# TSC_PROIECT_SCHEMATIC.net
KiCad netlist of a schematic drawn in EAGLE
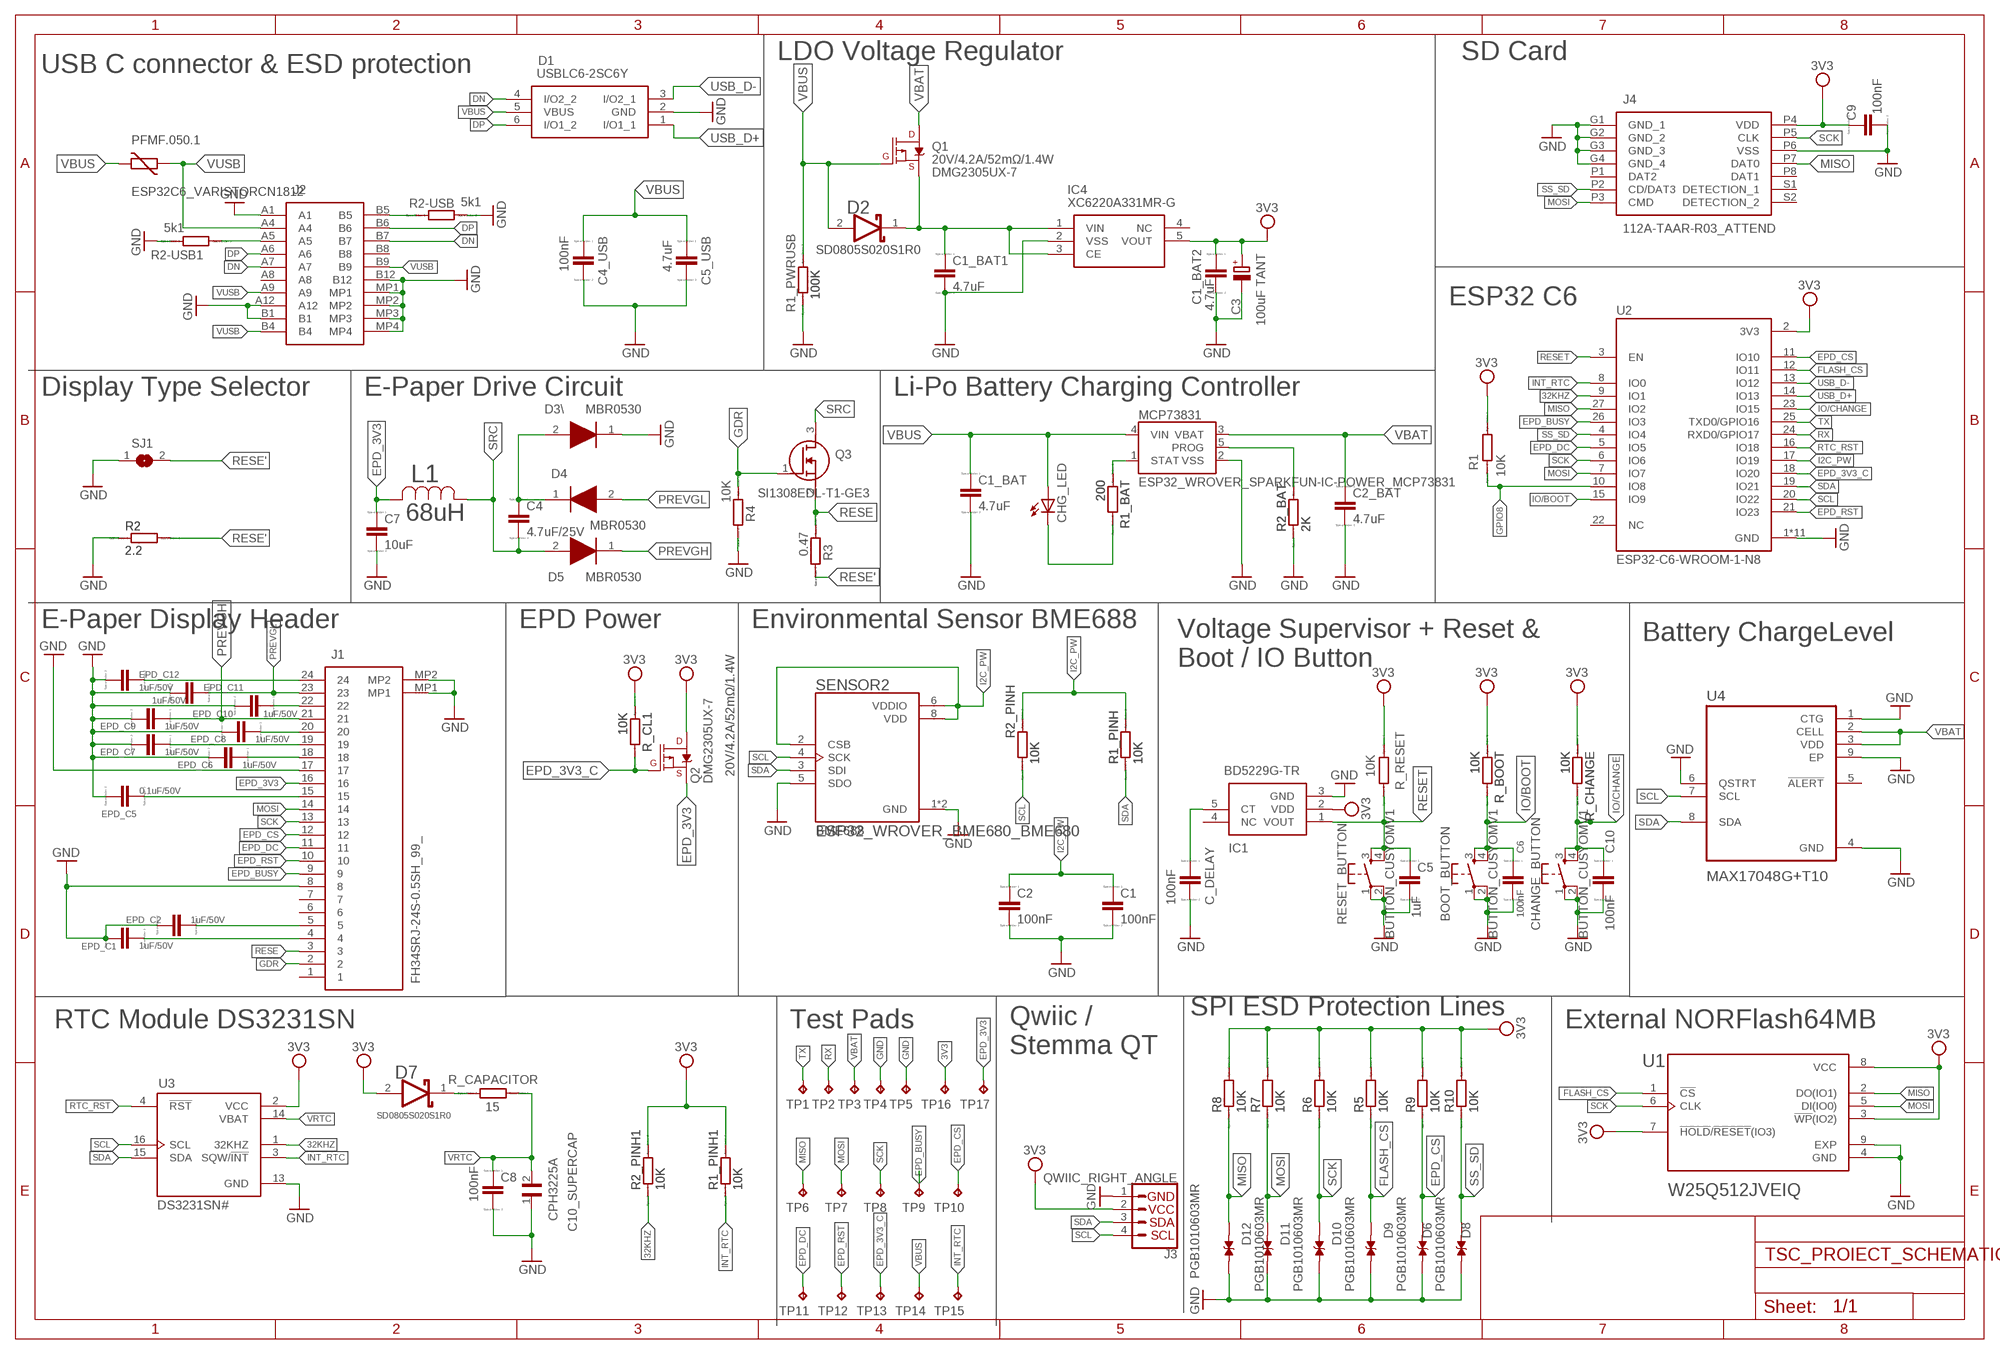
[diagram p0: schematic, sheet 1]

(export (version "E")
  (design (tool "Eeschema 10.0.6"))
  (components
    (comp (ref "BOOT_BUTTON")
      (value "BUTTON_CUSYOMV1")
      (footprint "eagle-import:MYBUTTON")
      (libsource (lib "eagle-import") (part "BUTTON_CUSYOMV1"))
    )
    (comp (ref "C1")
      (value "100nF")
      (footprint "eagle-import:ESP32_WROVER_EAGLE-LTSPICE_C0402")
      (libsource (lib "eagle-import") (part "ESP32_WROVER_EAGLE-LTSPICE_CC0402"))
    )
    (comp (ref "C1_BAT")
      (value "4.7uF")
      (footprint "eagle-import:ESP32_WROVER_EAGLE-LTSPICE_C0402")
      (libsource (lib "eagle-import") (part "EAGLE-LTSPICE_CC0402"))
    )
    (comp (ref "C1_BAT1")
      (value "4.7uF")
      (footprint "eagle-import:ESP32_WROVER_EAGLE-LTSPICE_C0402")
      (libsource (lib "eagle-import") (part "EAGLE-LTSPICE_CC0402"))
    )
    (comp (ref "C1_BAT2")
      (value "4.7uF")
      (footprint "eagle-import:ESP32_WROVER_EAGLE-LTSPICE_C0402")
      (libsource (lib "eagle-import") (part "ESP32_WROVER_EAGLE-LTSPICE_CC0402"))
    )
    (comp (ref "C2")
      (value "100nF")
      (footprint "eagle-import:ESP32_WROVER_EAGLE-LTSPICE_C0402")
      (libsource (lib "eagle-import") (part "ESP32_WROVER_EAGLE-LTSPICE_CC0402"))
    )
    (comp (ref "C2_BAT")
      (value "4.7uF")
      (footprint "eagle-import:ESP32_WROVER_EAGLE-LTSPICE_C0402")
      (libsource (lib "eagle-import") (part "EAGLE-LTSPICE_CC0402"))
    )
    (comp (ref "C3")
      (value "100uF TANT")
      (footprint "eagle-import:RCL_CT3528")
      (libsource (lib "eagle-import") (part "RCL_CPOL-EUCT3528"))
    )
    (comp (ref "C4")
      (value "4.7uF/25V")
      (footprint "eagle-import:ESP32_WROVER_EAGLE-LTSPICE_C0402")
      (libsource (lib "eagle-import") (part "ESP32_WROVER_EAGLE-LTSPICE_CC0402"))
    )
    (comp (ref "C4_USB")
      (value "100nF")
      (footprint "eagle-import:ESP32_WROVER_EAGLE-LTSPICE_C0402")
      (libsource (lib "eagle-import") (part "ESP32_WROVER_EAGLE-LTSPICE_CC0402"))
    )
    (comp (ref "C5")
      (value "1uF")
      (footprint "eagle-import:ESP32_WROVER_EAGLE-LTSPICE_C0402")
      (libsource (lib "eagle-import") (part "EAGLE-LTSPICE_CC0402"))
    )
    (comp (ref "C5_USB")
      (value "4.7uF")
      (footprint "eagle-import:ESP32_WROVER_EAGLE-LTSPICE_C0402")
      (libsource (lib "eagle-import") (part "ESP32_WROVER_EAGLE-LTSPICE_CC0402"))
    )
    (comp (ref "C6")
      (value "100nF")
      (footprint "eagle-import:ESP32_WROVER_EAGLE-LTSPICE_C0402")
      (libsource (lib "eagle-import") (part "EAGLE-LTSPICE_CC0402"))
    )
    (comp (ref "C7")
      (value "10uF")
      (footprint "eagle-import:ESP32_WROVER_EAGLE-LTSPICE_C0402")
      (libsource (lib "eagle-import") (part "ESP32_WROVER_EAGLE-LTSPICE_CC0402"))
    )
    (comp (ref "C8")
      (value "100nF")
      (footprint "eagle-import:ESP32_WROVER_EAGLE-LTSPICE_C0402")
      (libsource (lib "eagle-import") (part "ESP32_WROVER_EAGLE-LTSPICE_CC0402"))
    )
    (comp (ref "C9")
      (value "100nF")
      (footprint "eagle-import:ESP32_WROVER_EAGLE-LTSPICE_C0402")
      (libsource (lib "eagle-import") (part "EAGLE-LTSPICE_CC0402"))
    )
    (comp (ref "C10")
      (value "100nF")
      (footprint "eagle-import:ESP32_WROVER_EAGLE-LTSPICE_C0402")
      (libsource (lib "eagle-import") (part "EAGLE-LTSPICE_CC0402"))
    )
    (comp (ref "C10_SUPERCAP")
      (value "CPH3225A")
      (footprint "eagle-import:CAPCP3225X100N")
      (fields (field (name "MF") "Seiko Instruments"))
      (libsource (lib "eagle-import") (part "CPH3225A"))
    )
    (comp (ref "CHANGE_BUTTON")
      (value "BUTTON_CUSYOMV1")
      (footprint "eagle-import:MYBUTTON")
      (libsource (lib "eagle-import") (part "BUTTON_CUSYOMV1"))
    )
    (comp (ref "CHG_LED")
      (value "ADAFRUIT_LEDCHIP-LED0603")
      (footprint "eagle-import:ADAFRUIT_CHIP-LED0603")
      (libsource (lib "eagle-import") (part "ADAFRUIT_LEDCHIP-LED0603"))
    )
    (comp (ref "C_DELAY")
      (value "100nF")
      (footprint "eagle-import:ESP32_WROVER_EAGLE-LTSPICE_C0402")
      (libsource (lib "eagle-import") (part "EAGLE-LTSPICE_CC0402"))
    )
    (comp (ref "D1")
      (value "USBLC6-2SC6Y")
      (footprint "eagle-import:SOT95P280X145-6N")
      (fields (field (name "MF") "STMicroelectronics"))
      (libsource (lib "eagle-import") (part "USBLC6-2SC6Y"))
    )
    (comp (ref "D2")
      (value "ESP32_WROVER_AVX---SD0805S020S1R0_AVX_SD0805S020S1R0_0_0AVX_SD0805S020S1R0_0_0")
      (footprint "eagle-import:ESP32_WROVER_AVX---SD0805S020S1R0_AVX_SD0805S020S1R0_0")
      (fields
        (field (name "DIGIKEY_PART_NUMBER") "478-7800-1-ND")
        (field (name "MF") "AVX")
        (field (name "MOUSER_PART_NUMBER") "581-SD0805S020S1R0")
      )
      (libsource (lib "eagle-import") (part "ESP32_WROVER_AVX---SD0805S020S1R0_AVX_SD0805S020S1R0_0_0AVX_SD0805S020S1R0_0_0"))
    )
    (comp (ref "D3\\")
      (value "MBR0530")
      (footprint "eagle-import:SOD3716X135N")
      (fields (field (name "MF") "ON Semiconductor"))
      (libsource (lib "eagle-import") (part "MBR0530"))
    )
    (comp (ref "D4")
      (value "MBR0530")
      (footprint "eagle-import:SOD3716X135N")
      (fields (field (name "MF") "ON Semiconductor"))
      (libsource (lib "eagle-import") (part "MBR0530"))
    )
    (comp (ref "D5")
      (value "MBR0530")
      (footprint "eagle-import:SOD3716X135N")
      (fields (field (name "MF") "ON Semiconductor"))
      (libsource (lib "eagle-import") (part "MBR0530"))
    )
    (comp (ref "D6")
      (value "PGB1010603MR")
      (footprint "eagle-import:DIOC1608X36N")
      (fields (field (name "MF") "Littelfuse Inc."))
      (libsource (lib "eagle-import") (part "PGB1010603MR"))
    )
    (comp (ref "D7")
      (value "ESP32_WROVER_AVX---SD0805S020S1R0_AVX_SD0805S020S1R0_0_0AVX_SD0805S020S1R0_0_0")
      (footprint "eagle-import:ESP32_WROVER_AVX---SD0805S020S1R0_AVX_SD0805S020S1R0_0")
      (fields
        (field (name "DIGIKEY_PART_NUMBER") "478-7800-1-ND")
        (field (name "MF") "AVX")
        (field (name "MOUSER_PART_NUMBER") "581-SD0805S020S1R0")
      )
      (libsource (lib "eagle-import") (part "ESP32_WROVER_AVX---SD0805S020S1R0_AVX_SD0805S020S1R0_0_0AVX_SD0805S020S1R0_0_0"))
    )
    (comp (ref "D8")
      (value "PGB1010603MR")
      (footprint "eagle-import:DIOC1608X36N")
      (fields (field (name "MF") "Littelfuse Inc."))
      (libsource (lib "eagle-import") (part "PGB1010603MR"))
    )
    (comp (ref "D9")
      (value "PGB1010603MR")
      (footprint "eagle-import:DIOC1608X36N")
      (fields (field (name "MF") "Littelfuse Inc."))
      (libsource (lib "eagle-import") (part "PGB1010603MR"))
    )
    (comp (ref "D10")
      (value "PGB1010603MR")
      (footprint "eagle-import:DIOC1608X36N")
      (fields (field (name "MF") "Littelfuse Inc."))
      (libsource (lib "eagle-import") (part "PGB1010603MR"))
    )
    (comp (ref "D11")
      (value "PGB1010603MR")
      (footprint "eagle-import:DIOC1608X36N")
      (fields (field (name "MF") "Littelfuse Inc."))
      (libsource (lib "eagle-import") (part "PGB1010603MR"))
    )
    (comp (ref "D12")
      (value "PGB1010603MR")
      (footprint "eagle-import:DIOC1608X36N")
      (fields (field (name "MF") "Littelfuse Inc."))
      (libsource (lib "eagle-import") (part "PGB1010603MR"))
    )
    (comp (ref "EPD_C1")
      (value "1uF/50V")
      (footprint "eagle-import:ESP32_WROVER_EAGLE-LTSPICE_C0402")
      (libsource (lib "eagle-import") (part "EAGLE-LTSPICE_CC0402"))
    )
    (comp (ref "EPD_C2")
      (value "1uF/50V")
      (footprint "eagle-import:ESP32_WROVER_EAGLE-LTSPICE_C0402")
      (libsource (lib "eagle-import") (part "EAGLE-LTSPICE_CC0402"))
    )
    (comp (ref "EPD_C5")
      (value "0.1uF/50V")
      (footprint "eagle-import:ESP32_WROVER_EAGLE-LTSPICE_C0402")
      (libsource (lib "eagle-import") (part "ESP32_WROVER_EAGLE-LTSPICE_CC0402"))
    )
    (comp (ref "EPD_C6")
      (value "1uF/50V")
      (footprint "eagle-import:ESP32_WROVER_EAGLE-LTSPICE_C0402")
      (libsource (lib "eagle-import") (part "ESP32_WROVER_EAGLE-LTSPICE_CC0402"))
    )
    (comp (ref "EPD_C7")
      (value "1uF/50V")
      (footprint "eagle-import:ESP32_WROVER_EAGLE-LTSPICE_C0402")
      (libsource (lib "eagle-import") (part "ESP32_WROVER_EAGLE-LTSPICE_CC0402"))
    )
    (comp (ref "EPD_C8")
      (value "1uF/50V")
      (footprint "eagle-import:ESP32_WROVER_EAGLE-LTSPICE_C0402")
      (libsource (lib "eagle-import") (part "ESP32_WROVER_EAGLE-LTSPICE_CC0402"))
    )
    (comp (ref "EPD_C9")
      (value "1uF/50V")
      (footprint "eagle-import:ESP32_WROVER_EAGLE-LTSPICE_C0402")
      (libsource (lib "eagle-import") (part "ESP32_WROVER_EAGLE-LTSPICE_CC0402"))
    )
    (comp (ref "EPD_C10")
      (value "1uF/50V")
      (footprint "eagle-import:ESP32_WROVER_EAGLE-LTSPICE_C0402")
      (libsource (lib "eagle-import") (part "ESP32_WROVER_EAGLE-LTSPICE_CC0402"))
    )
    (comp (ref "EPD_C11")
      (value "1uF/50V")
      (footprint "eagle-import:ESP32_WROVER_EAGLE-LTSPICE_C0402")
      (libsource (lib "eagle-import") (part "ESP32_WROVER_EAGLE-LTSPICE_CC0402"))
    )
    (comp (ref "EPD_C12")
      (value "1uF/50V")
      (footprint "eagle-import:ESP32_WROVER_EAGLE-LTSPICE_C0402")
      (libsource (lib "eagle-import") (part "ESP32_WROVER_EAGLE-LTSPICE_CC0402"))
    )
    (comp (ref "IC1")
      (value "BD5229G-TR")
      (footprint "eagle-import:SOT95P280X125-5N")
      (fields (field (name "MOUSER_PART_NUMBER") "755-BD5229G-TR"))
      (libsource (lib "eagle-import") (part "BD5229G-TR"))
    )
    (comp (ref "IC4")
      (value "XC6220A331MR-G")
      (footprint "eagle-import:SOT95P280X120-5N")
      (fields (field (name "MOUSER_PART_NUMBER") "865-XC6220A331MR-G"))
      (libsource (lib "eagle-import") (part "XC6220A331MR-G"))
    )
    (comp (ref "J1")
      (value "FH34SRJ-24S-0.5SH_99_")
      (footprint "eagle-import:FH34SRJ24S05SH99")
      (fields
        (field (name "MANUFACTURER_PART_NUMBER") "FH34SRJ-24S-0.5SH(99)")
        (field (name "MOUSER_PART_NUMBER") "798-FH34SRJ24S05SH99")
      )
      (libsource (lib "eagle-import") (part "FH34SRJ-24S-0.5SH_99_"))
    )
    (comp (ref "J2")
      (value "SAMACSYS_PARTS_USB4110-GF-A")
      (footprint "eagle-import:SAMACSYS_PARTS_USB4110GFA")
      (fields
        (field (name "MANUFACTURER_PART_NUMBER") "USB4110-GF-A")
        (field (name "MOUSER_PART_NUMBER") "640-USB4110-GF-A")
      )
      (libsource (lib "eagle-import") (part "SAMACSYS_PARTS_USB4110-GF-A"))
    )
    (comp (ref "J3")
      (value "QWIIC_RIGHT_ANGLE")
      (footprint "eagle-import:JST04_1MM_RA")
      (libsource (lib "eagle-import") (part "QWIIC_CONNECTORJS-1MM"))
    )
    (comp (ref "J4")
      (value "112A-TAAR-R03_ATTEND")
      (footprint "eagle-import:112ATAARR03ATTEND")
      (fields (field (name "MANUFACTURER_PART_NUMBER") "112A-TAAR-R03 ATTEND"))
      (libsource (lib "eagle-import") (part "112A-TAAR-R03_ATTEND"))
    )
    (comp (ref "L1")
      (value "68uH")
      (footprint "eagle-import:IND_4828-WE-TPC_WRE")
      (fields
        (field (name "MANUFACTURER_PART_NUMBER") "744043680")
        (field (name "COPYRIGHT") "Copyright (C) 2024 Ultra Librarian. All rights reserved.")
      )
      (libsource (lib "eagle-import") (part "744043680IND_4828-WE-TPC_WRE"))
    )
    (comp (ref "MCP73831")
      (value "ESP32_WROVER_SPARKFUN-IC-POWER_MCP73831")
      (footprint "eagle-import:ESP32_WROVER_SPARKFUN-IC-POWER_SOT23-5")
      (libsource (lib "eagle-import") (part "ESP32_WROVER_SPARKFUN-IC-POWER_MCP73831"))
    )
    (comp (ref "PFMF.050.1")
      (value "ESP32C6_VARISTORCN1812")
      (footprint "eagle-import:ESP32C6_VARISTOR_CT_CN1812")
      (libsource (lib "eagle-import") (part "ESP32C6_VARISTORCN1812"))
    )
    (comp (ref "Q1")
      (value "20V/4.2A/52mΩ/1.4W")
      (footprint "eagle-import:ESP32_WROVER_SPARKFUN-DISCRETESEMI_SOT23-3")
      (libsource (lib "eagle-import") (part "ESP32_WROVER_SPARKFUN-DISCRETESEMI_MOSFET_PCH-DMG2305UX-7"))
    )
    (comp (ref "Q2")
      (value "20V/4.2A/52mΩ/1.4W")
      (footprint "eagle-import:ESP32_WROVER_SPARKFUN-DISCRETESEMI_SOT23-3")
      (libsource (lib "eagle-import") (part "ESP32_WROVER_SPARKFUN-DISCRETESEMI_MOSFET_PCH-DMG2305UX-7"))
    )
    (comp (ref "Q3")
      (value "SI1308EDL-T1-GE3")
      (footprint "eagle-import:SOT65P210X110-3N")
      (fields (field (name "MF") "Vishay Siliconix"))
      (libsource (lib "eagle-import") (part "SI1308EDL-T1-GE3"))
    )
    (comp (ref "R1")
      (value "10K")
      (footprint "eagle-import:ESP32_WROVER_EAGLE-LTSPICE_R0402")
      (libsource (lib "eagle-import") (part "ESP32_WROVER_EAGLE-LTSPICE_RR0402"))
    )
    (comp (ref "R1_BAT")
      (value "200")
      (footprint "eagle-import:ESP32_WROVER_EAGLE-LTSPICE_R0402")
      (libsource (lib "eagle-import") (part "ESP32_WROVER_EAGLE-LTSPICE_RR0402"))
    )
    (comp (ref "R1_PINH")
      (value "10K")
      (footprint "eagle-import:ESP32_WROVER_EAGLE-LTSPICE_R0402")
      (libsource (lib "eagle-import") (part "ESP32_WROVER_EAGLE-LTSPICE_RR0402"))
    )
    (comp (ref "R1_PINH1")
      (value "10K")
      (footprint "eagle-import:ESP32_WROVER_EAGLE-LTSPICE_R0402")
      (libsource (lib "eagle-import") (part "ESP32_WROVER_EAGLE-LTSPICE_RR0402"))
    )
    (comp (ref "R1_PWRUSB")
      (value "100K")
      (footprint "eagle-import:ESP32_WROVER_EAGLE-LTSPICE_R0402")
      (libsource (lib "eagle-import") (part "ESP32_WROVER_EAGLE-LTSPICE_RR0402"))
    )
    (comp (ref "R2")
      (value "2.2")
      (footprint "eagle-import:ESP32_WROVER_EAGLE-LTSPICE_R0402")
      (libsource (lib "eagle-import") (part "ESP32_WROVER_EAGLE-LTSPICE_RR0402"))
    )
    (comp (ref "R2-USB")
      (value "5k1")
      (footprint "eagle-import:ESP32_WROVER_EAGLE-LTSPICE_R0402")
      (libsource (lib "eagle-import") (part "ESP32_WROVER_EAGLE-LTSPICE_RR0402"))
    )
    (comp (ref "R2-USB1")
      (value "5k1")
      (footprint "eagle-import:ESP32_WROVER_EAGLE-LTSPICE_R0402")
      (libsource (lib "eagle-import") (part "ESP32_WROVER_EAGLE-LTSPICE_RR0402"))
    )
    (comp (ref "R2_BAT")
      (value "2K")
      (footprint "eagle-import:ESP32_WROVER_EAGLE-LTSPICE_R0402")
      (libsource (lib "eagle-import") (part "ESP32_WROVER_EAGLE-LTSPICE_RR0402"))
    )
    (comp (ref "R2_PINH")
      (value "10K")
      (footprint "eagle-import:ESP32_WROVER_EAGLE-LTSPICE_R0402")
      (libsource (lib "eagle-import") (part "ESP32_WROVER_EAGLE-LTSPICE_RR0402"))
    )
    (comp (ref "R2_PINH1")
      (value "10K")
      (footprint "eagle-import:ESP32_WROVER_EAGLE-LTSPICE_R0402")
      (libsource (lib "eagle-import") (part "ESP32_WROVER_EAGLE-LTSPICE_RR0402"))
    )
    (comp (ref "R3")
      (value "0.47")
      (footprint "eagle-import:ESP32_WROVER_EAGLE-LTSPICE_R0402")
      (libsource (lib "eagle-import") (part "ESP32_WROVER_EAGLE-LTSPICE_RR0402"))
    )
    (comp (ref "R4")
      (value "10K")
      (footprint "eagle-import:ESP32_WROVER_EAGLE-LTSPICE_R0402")
      (libsource (lib "eagle-import") (part "ESP32_WROVER_EAGLE-LTSPICE_RR0402"))
    )
    (comp (ref "R5")
      (value "10K")
      (footprint "eagle-import:ESP32_WROVER_EAGLE-LTSPICE_R0402")
      (libsource (lib "eagle-import") (part "ESP32_WROVER_EAGLE-LTSPICE_RR0402"))
    )
    (comp (ref "R6")
      (value "10K")
      (footprint "eagle-import:ESP32_WROVER_EAGLE-LTSPICE_R0402")
      (libsource (lib "eagle-import") (part "ESP32_WROVER_EAGLE-LTSPICE_RR0402"))
    )
    (comp (ref "R7")
      (value "10K")
      (footprint "eagle-import:ESP32_WROVER_EAGLE-LTSPICE_R0402")
      (libsource (lib "eagle-import") (part "ESP32_WROVER_EAGLE-LTSPICE_RR0402"))
    )
    (comp (ref "R8")
      (value "10K")
      (footprint "eagle-import:ESP32_WROVER_EAGLE-LTSPICE_R0402")
      (libsource (lib "eagle-import") (part "ESP32_WROVER_EAGLE-LTSPICE_RR0402"))
    )
    (comp (ref "R9")
      (value "10K")
      (footprint "eagle-import:ESP32_WROVER_EAGLE-LTSPICE_R0402")
      (libsource (lib "eagle-import") (part "ESP32_WROVER_EAGLE-LTSPICE_RR0402"))
    )
    (comp (ref "R10")
      (value "10K")
      (footprint "eagle-import:ESP32_WROVER_EAGLE-LTSPICE_R0402")
      (libsource (lib "eagle-import") (part "ESP32_WROVER_EAGLE-LTSPICE_RR0402"))
    )
    (comp (ref "RESET_BUTTON")
      (value "BUTTON_CUSYOMV1")
      (footprint "eagle-import:MYBUTTON")
      (libsource (lib "eagle-import") (part "BUTTON_CUSYOMV1"))
    )
    (comp (ref "R_BOOT")
      (value "10K")
      (footprint "eagle-import:ESP32_WROVER_EAGLE-LTSPICE_R0402")
      (libsource (lib "eagle-import") (part "ESP32_WROVER_EAGLE-LTSPICE_RR0402"))
    )
    (comp (ref "R_CAPACITOR")
      (value "15")
      (footprint "eagle-import:ESP32_WROVER_EAGLE-LTSPICE_R0402")
      (libsource (lib "eagle-import") (part "ESP32_WROVER_EAGLE-LTSPICE_RR0402"))
    )
    (comp (ref "R_CHANGE")
      (value "10K")
      (footprint "eagle-import:ESP32_WROVER_EAGLE-LTSPICE_R0402")
      (libsource (lib "eagle-import") (part "ESP32_WROVER_EAGLE-LTSPICE_RR0402"))
    )
    (comp (ref "R_CL1")
      (value "10K")
      (footprint "eagle-import:ESP32_WROVER_EAGLE-LTSPICE_R0402")
      (libsource (lib "eagle-import") (part "ESP32_WROVER_EAGLE-LTSPICE_RR0402"))
    )
    (comp (ref "R_RESET")
      (value "10K")
      (footprint "eagle-import:ESP32_WROVER_EAGLE-LTSPICE_R0402")
      (libsource (lib "eagle-import") (part "ESP32_WROVER_EAGLE-LTSPICE_RR0402"))
    )
    (comp (ref "SENSOR2")
      (value "ESP32_WROVER_BME680_BME680")
      (footprint "eagle-import:ESP32_WROVER_BME680_PSON80P300X300X100-8N")
      (fields (field (name "MF") "Bosch Sensortec") (field (name "MP") "BME680"))
      (libsource (lib "eagle-import") (part "ESP32_WROVER_BME680_BME680"))
    )
    (comp (ref "SJ1") (value "SJ") (footprint "eagle-import:SJ") (libsource (lib "eagle-import") (part "SJ")))
    (comp (ref "TP1")
      (value "TPTP20R")
      (footprint "eagle-import:TP20R")
      (libsource (lib "eagle-import") (part "TPTP20R"))
    )
    (comp (ref "TP2")
      (value "TPTP20R")
      (footprint "eagle-import:TP20R")
      (libsource (lib "eagle-import") (part "TPTP20R"))
    )
    (comp (ref "TP3")
      (value "TPTP20R")
      (footprint "eagle-import:TP20R")
      (libsource (lib "eagle-import") (part "TPTP20R"))
    )
    (comp (ref "TP4")
      (value "TPTP20R")
      (footprint "eagle-import:TP20R")
      (libsource (lib "eagle-import") (part "TPTP20R"))
    )
    (comp (ref "TP5")
      (value "TPTP20R")
      (footprint "eagle-import:TP20R")
      (libsource (lib "eagle-import") (part "TPTP20R"))
    )
    (comp (ref "TP6")
      (value "TPTP20R")
      (footprint "eagle-import:TP20R")
      (libsource (lib "eagle-import") (part "TPTP20R"))
    )
    (comp (ref "TP7")
      (value "TPTP20R")
      (footprint "eagle-import:TP20R")
      (libsource (lib "eagle-import") (part "TPTP20R"))
    )
    (comp (ref "TP8")
      (value "TPTP20R")
      (footprint "eagle-import:TP20R")
      (libsource (lib "eagle-import") (part "TPTP20R"))
    )
    (comp (ref "TP9")
      (value "TPTP20R")
      (footprint "eagle-import:TP20R")
      (libsource (lib "eagle-import") (part "TPTP20R"))
    )
    (comp (ref "TP10")
      (value "TPTP20R")
      (footprint "eagle-import:TP20R")
      (libsource (lib "eagle-import") (part "TPTP20R"))
    )
    (comp (ref "TP11")
      (value "TPTP20R")
      (footprint "eagle-import:TP20R")
      (libsource (lib "eagle-import") (part "TPTP20R"))
    )
    (comp (ref "TP12")
      (value "TPTP20R")
      (footprint "eagle-import:TP20R")
      (libsource (lib "eagle-import") (part "TPTP20R"))
    )
    (comp (ref "TP13")
      (value "TPTP20R")
      (footprint "eagle-import:TP20R")
      (libsource (lib "eagle-import") (part "TPTP20R"))
    )
    (comp (ref "TP14")
      (value "TPTP20R")
      (footprint "eagle-import:TP20R")
      (libsource (lib "eagle-import") (part "TPTP20R"))
    )
    (comp (ref "TP15")
      (value "TPTP20R")
      (footprint "eagle-import:TP20R")
      (libsource (lib "eagle-import") (part "TPTP20R"))
    )
    (comp (ref "TP16")
      (value "TPTP20R")
      (footprint "eagle-import:TP20R")
      (libsource (lib "eagle-import") (part "TPTP20R"))
    )
    (comp (ref "TP17")
      (value "TPTP20R")
      (footprint "eagle-import:TP20R")
      (libsource (lib "eagle-import") (part "TPTP20R"))
    )
    (comp (ref "U1")
      (value "W25Q512JVEIQ")
      (footprint "eagle-import:SON127P600X800X80-9N")
      (fields (field (name "MF") "Winbond Electronics"))
      (libsource (lib "eagle-import") (part "W25Q512JVEIQ"))
    )
    (comp (ref "U2")
      (value "ESP32-C6-WROOM-1-N8")
      (footprint "eagle-import:XCVR_ESP32-C6-WROOM-1-N8")
      (fields (field (name "MF") "Espressif Systems"))
      (libsource (lib "eagle-import") (part "ESP32-C6-WROOM-1-N8"))
    )
    (comp (ref "U3")
      (value "DS3231SN#")
      (footprint "eagle-import:SOIC127P1032X265-16N")
      (fields (field (name "MF") "Analog Devices"))
      (libsource (lib "eagle-import") (part "DS3231SN#"))
    )
    (comp (ref "U4")
      (value "MAX17048G+T10")
      (footprint "eagle-import:SON50P200X200X80-9N")
      (fields (field (name "MF") "Analog Devices"))
      (libsource (lib "eagle-import") (part "MAX17048G+T10"))
    )
  )
  (nets
    (net (code "1") (name "3V3") (class "Default")
      (node (ref "C1_BAT2") (pin "1") (pinfunction "1_1") (pintype "passive"))
      (node (ref "C3") (pin "+") (pinfunction "+_+") (pintype "passive"))
      (node (ref "C9") (pin "1") (pinfunction "1_1") (pintype "passive"))
      (node (ref "D7") (pin "2") (pinfunction "ANODE_2") (pintype "bidirectional"))
      (node (ref "IC1") (pin "2") (pinfunction "VDD_2") (pintype "bidirectional"))
      (node (ref "IC4") (pin "5") (pinfunction "VOUT_5") (pintype "bidirectional"))
      (node (ref "J3") (pin "2") (pinfunction "2_2") (pintype "power_in"))
      (node (ref "J4") (pin "P4") (pinfunction "VDD_P4") (pintype "bidirectional"))
      (node (ref "Q2") (pin "3") (pinfunction "D_3") (pintype "bidirectional"))
      (node (ref "R1") (pin "1") (pinfunction "1_1") (pintype "passive"))
      (node (ref "R10") (pin "2") (pinfunction "2_2") (pintype "passive"))
      (node (ref "R1_PINH1") (pin "2") (pinfunction "2_2") (pintype "passive"))
      (node (ref "R2_PINH1") (pin "2") (pinfunction "2_2") (pintype "passive"))
      (node (ref "R5") (pin "2") (pinfunction "2_2") (pintype "passive"))
      (node (ref "R6") (pin "2") (pinfunction "2_2") (pintype "passive"))
      (node (ref "R7") (pin "2") (pinfunction "2_2") (pintype "passive"))
      (node (ref "R8") (pin "2") (pinfunction "2_2") (pintype "passive"))
      (node (ref "R9") (pin "2") (pinfunction "2_2") (pintype "passive"))
      (node (ref "R_BOOT") (pin "1") (pinfunction "1_1") (pintype "passive"))
      (node (ref "R_CHANGE") (pin "1") (pinfunction "1_1") (pintype "passive"))
      (node (ref "R_CL1") (pin "1") (pinfunction "1_1") (pintype "passive"))
      (node (ref "R_RESET") (pin "1") (pinfunction "1_1") (pintype "passive"))
      (node (ref "TP16") (pin "TP") (pinfunction "TP_TP") (pintype "input"))
      (node (ref "U1") (pin "3") (pinfunction "~{WP}(IO2)_3") (pintype "bidirectional"))
      (node (ref "U1") (pin "7") (pinfunction "~{HOLD}/~{RESET}(IO3)_7") (pintype "bidirectional"))
      (node (ref "U1") (pin "8") (pinfunction "VCC_8") (pintype "power_in"))
      (node (ref "U2") (pin "2") (pinfunction "3V3_2") (pintype "power_in"))
      (node (ref "U3") (pin "2") (pinfunction "VCC_2") (pintype "power_in"))
    )
    (net (code "2") (name "32KHZ") (class "Default")
      (node (ref "R2_PINH1") (pin "1") (pinfunction "1_1") (pintype "passive"))
      (node (ref "U2") (pin "9") (pinfunction "IO1_9") (pintype "bidirectional"))
      (node (ref "U3") (pin "1") (pinfunction "32KHZ_1") (pintype "output"))
    )
    (net (code "3") (name "DN") (class "Default")
      (node (ref "D1") (pin "4") (pinfunction "I/O2_2_4") (pintype "bidirectional"))
      (node (ref "J2") (pin "A7") (pinfunction "A7_A7") (pintype "bidirectional"))
      (node (ref "J2") (pin "B7") (pinfunction "B7_B7") (pintype "bidirectional"))
    )
    (net (code "4") (name "DP") (class "Default")
      (node (ref "D1") (pin "6") (pinfunction "I/O1_2_6") (pintype "bidirectional"))
      (node (ref "J2") (pin "A6") (pinfunction "A6_A6") (pintype "bidirectional"))
      (node (ref "J2") (pin "B6") (pinfunction "B6_B6") (pintype "bidirectional"))
    )
    (net (code "5") (name "EPD_3V3") (class "Default")
      (node (ref "C7") (pin "1") (pinfunction "1_1") (pintype "passive"))
      (node (ref "J1") (pin "16") (pinfunction "16_16") (pintype "bidirectional"))
      (node (ref "L1") (pin "2") (pinfunction "2_2") (pintype "passive"))
      (node (ref "Q2") (pin "2") (pinfunction "S_2") (pintype "bidirectional"))
      (node (ref "TP17") (pin "TP") (pinfunction "TP_TP") (pintype "input"))
    )
    (net (code "6") (name "EPD_3V3_C") (class "Default")
      (node (ref "Q2") (pin "1") (pinfunction "G_1") (pintype "bidirectional"))
      (node (ref "R_CL1") (pin "2") (pinfunction "2_2") (pintype "passive"))
      (node (ref "TP13") (pin "TP") (pinfunction "TP_TP") (pintype "input"))
      (node (ref "U2") (pin "18") (pinfunction "IO20_18") (pintype "bidirectional"))
    )
    (net (code "7") (name "EPD_BUSY") (class "Default")
      (node (ref "J1") (pin "9") (pinfunction "9_9") (pintype "bidirectional"))
      (node (ref "TP9") (pin "TP") (pinfunction "TP_TP") (pintype "input"))
      (node (ref "U2") (pin "26") (pinfunction "IO3_26") (pintype "bidirectional"))
    )
    (net (code "8") (name "EPD_CS") (class "Default")
      (node (ref "D6") (pin "1") (pinfunction "1_1") (pintype "passive"))
      (node (ref "J1") (pin "12") (pinfunction "12_12") (pintype "bidirectional"))
      (node (ref "R9") (pin "1") (pinfunction "1_1") (pintype "passive"))
      (node (ref "TP10") (pin "TP") (pinfunction "TP_TP") (pintype "input"))
      (node (ref "U2") (pin "11") (pinfunction "IO10_11") (pintype "bidirectional"))
    )
    (net (code "9") (name "EPD_DC") (class "Default")
      (node (ref "J1") (pin "11") (pinfunction "11_11") (pintype "bidirectional"))
      (node (ref "TP11") (pin "TP") (pinfunction "TP_TP") (pintype "input"))
      (node (ref "U2") (pin "5") (pinfunction "IO5_5") (pintype "bidirectional"))
    )
    (net (code "10") (name "EPD_RST") (class "Default")
      (node (ref "J1") (pin "10") (pinfunction "10_10") (pintype "bidirectional"))
      (node (ref "TP12") (pin "TP") (pinfunction "TP_TP") (pintype "input"))
      (node (ref "U2") (pin "21") (pinfunction "IO23_21") (pintype "bidirectional"))
    )
    (net (code "11") (name "FLASH_CS") (class "Default")
      (node (ref "D9") (pin "1") (pinfunction "1_1") (pintype "passive"))
      (node (ref "R5") (pin "1") (pinfunction "1_1") (pintype "passive"))
      (node (ref "U1") (pin "1") (pinfunction "~{CS}_1") (pintype "input"))
      (node (ref "U2") (pin "12") (pinfunction "IO11_12") (pintype "bidirectional"))
    )
    (net (code "12") (name "GDR") (class "Default")
      (node (ref "J1") (pin "2") (pinfunction "2_2") (pintype "bidirectional"))
      (node (ref "Q3") (pin "1") (pinfunction "G_1") (pintype "bidirectional"))
      (node (ref "R4") (pin "1") (pinfunction "1_1") (pintype "passive"))
    )
    (net (code "13") (name "GND") (class "Default")
      (node (ref "BOOT_BUTTON") (pin "1") (pinfunction "1_1") (pintype "passive"))
      (node (ref "BOOT_BUTTON") (pin "2") (pinfunction "2_2") (pintype "passive"))
      (node (ref "C1") (pin "2") (pinfunction "2_2") (pintype "passive"))
      (node (ref "C10") (pin "2") (pinfunction "2_2") (pintype "passive"))
      (node (ref "C10_SUPERCAP") (pin "1") (pinfunction "1_1") (pintype "passive"))
      (node (ref "C1_BAT") (pin "2") (pinfunction "2_2") (pintype "passive"))
      (node (ref "C1_BAT1") (pin "2") (pinfunction "2_2") (pintype "passive"))
      (node (ref "C1_BAT2") (pin "2") (pinfunction "2_2") (pintype "passive"))
      (node (ref "C2") (pin "2") (pinfunction "2_2") (pintype "passive"))
      (node (ref "C2_BAT") (pin "2") (pinfunction "2_2") (pintype "passive"))
      (node (ref "C3") (pin "-") (pinfunction "-_-") (pintype "passive"))
      (node (ref "C4_USB") (pin "2") (pinfunction "2_2") (pintype "passive"))
      (node (ref "C5") (pin "2") (pinfunction "2_2") (pintype "passive"))
      (node (ref "C5_USB") (pin "2") (pinfunction "2_2") (pintype "passive"))
      (node (ref "C6") (pin "2") (pinfunction "2_2") (pintype "passive"))
      (node (ref "C7") (pin "2") (pinfunction "2_2") (pintype "passive"))
      (node (ref "C8") (pin "2") (pinfunction "2_2") (pintype "passive"))
      (node (ref "C9") (pin "2") (pinfunction "2_2") (pintype "passive"))
      (node (ref "CHANGE_BUTTON") (pin "1") (pinfunction "1_1") (pintype "passive"))
      (node (ref "CHANGE_BUTTON") (pin "2") (pinfunction "2_2") (pintype "passive"))
      (node (ref "C_DELAY") (pin "2") (pinfunction "2_2") (pintype "passive"))
      (node (ref "D1") (pin "2") (pinfunction "GND_2") (pintype "bidirectional"))
      (node (ref "D10") (pin "2") (pinfunction "2_2") (pintype "passive"))
      (node (ref "D11") (pin "2") (pinfunction "2_2") (pintype "passive"))
      (node (ref "D12") (pin "2") (pinfunction "2_2") (pintype "passive"))
      (node (ref "D3\\") (pin "1") (pinfunction "K_1") (pintype "bidirectional"))
      (node (ref "D6") (pin "2") (pinfunction "2_2") (pintype "passive"))
      (node (ref "D8") (pin "2") (pinfunction "2_2") (pintype "passive"))
      (node (ref "D9") (pin "2") (pinfunction "2_2") (pintype "passive"))
      (node (ref "EPD_C1") (pin "2") (pinfunction "2_2") (pintype "passive"))
      (node (ref "EPD_C10") (pin "2") (pinfunction "2_2") (pintype "passive"))
      (node (ref "EPD_C11") (pin "2") (pinfunction "2_2") (pintype "passive"))
      (node (ref "EPD_C12") (pin "2") (pinfunction "2_2") (pintype "passive"))
      (node (ref "EPD_C2") (pin "2") (pinfunction "2_2") (pintype "passive"))
      (node (ref "EPD_C5") (pin "2") (pinfunction "2_2") (pintype "passive"))
      (node (ref "EPD_C6") (pin "2") (pinfunction "2_2") (pintype "passive"))
      (node (ref "EPD_C7") (pin "2") (pinfunction "2_2") (pintype "passive"))
      (node (ref "EPD_C8") (pin "2") (pinfunction "2_2") (pintype "passive"))
      (node (ref "EPD_C9") (pin "2") (pinfunction "2_2") (pintype "passive"))
      (node (ref "IC1") (pin "3") (pinfunction "GND_3") (pintype "bidirectional"))
      (node (ref "IC4") (pin "2") (pinfunction "VSS_2") (pintype "bidirectional"))
      (node (ref "J1") (pin "17") (pinfunction "17_17") (pintype "bidirectional"))
      (node (ref "J1") (pin "8") (pinfunction "8_8") (pintype "bidirectional"))
      (node (ref "J1") (pin "MP1") (pinfunction "MP1_MP1") (pintype "bidirectional"))
      (node (ref "J1") (pin "MP2") (pinfunction "MP2_MP2") (pintype "bidirectional"))
      (node (ref "J2") (pin "A1") (pinfunction "A1_A1") (pintype "bidirectional"))
      (node (ref "J2") (pin "A12") (pinfunction "A12_A12") (pintype "bidirectional"))
      (node (ref "J2") (pin "B1") (pinfunction "B1_B1") (pintype "bidirectional"))
      (node (ref "J2") (pin "B12") (pinfunction "B12_B12") (pintype "bidirectional"))
      (node (ref "J2") (pin "MP1") (pinfunction "MP1_MP1") (pintype "bidirectional"))
      (node (ref "J2") (pin "MP2") (pinfunction "MP2_MP2") (pintype "bidirectional"))
      (node (ref "J2") (pin "MP3") (pinfunction "MP3_MP3") (pintype "bidirectional"))
      (node (ref "J2") (pin "MP4") (pinfunction "MP4_MP4") (pintype "bidirectional"))
      (node (ref "J3") (pin "1") (pinfunction "1_1") (pintype "power_in"))
      (node (ref "J4") (pin "G1") (pinfunction "GND_1_G1") (pintype "bidirectional"))
      (node (ref "J4") (pin "G2") (pinfunction "GND_2_G2") (pintype "bidirectional"))
      (node (ref "J4") (pin "G3") (pinfunction "GND_3_G3") (pintype "bidirectional"))
      (node (ref "J4") (pin "G4") (pinfunction "GND_4_G4") (pintype "bidirectional"))
      (node (ref "J4") (pin "P6") (pinfunction "VSS_P6") (pintype "bidirectional"))
      (node (ref "MCP73831") (pin "2") (pinfunction "VSS_2") (pintype "power_in"))
      (node (ref "R1_PWRUSB") (pin "1") (pinfunction "1_1") (pintype "passive"))
      (node (ref "R2") (pin "1") (pinfunction "1_1") (pintype "passive"))
      (node (ref "R2-USB") (pin "2") (pinfunction "2_2") (pintype "passive"))
      (node (ref "R2-USB1") (pin "1") (pinfunction "1_1") (pintype "passive"))
      (node (ref "R2_BAT") (pin "1") (pinfunction "1_1") (pintype "passive"))
      (node (ref "R4") (pin "2") (pinfunction "2_2") (pintype "passive"))
      (node (ref "RESET_BUTTON") (pin "1") (pinfunction "1_1") (pintype "passive"))
      (node (ref "RESET_BUTTON") (pin "2") (pinfunction "2_2") (pintype "passive"))
      (node (ref "SENSOR2") (pin "1") (pinfunction "GND_1") (pintype "power_in"))
      (node (ref "SENSOR2") (pin "5") (pinfunction "SDO_5") (pintype "bidirectional"))
      (node (ref "SENSOR2") (pin "7") (pinfunction "GND_7") (pintype "power_in"))
      (node (ref "SJ1") (pin "1") (pinfunction "1_1") (pintype "passive"))
      (node (ref "TP4") (pin "TP") (pinfunction "TP_TP") (pintype "input"))
      (node (ref "TP5") (pin "TP") (pinfunction "TP_TP") (pintype "input"))
      (node (ref "U1") (pin "4") (pinfunction "GND_4") (pintype "power_in"))
      (node (ref "U1") (pin "9") (pinfunction "EXP_9") (pintype "passive"))
      (node (ref "U2") (pin "1") (pinfunction "GND_1") (pintype "power_in"))
      (node (ref "U2") (pin "28") (pinfunction "GND_28") (pintype "power_in"))
      (node (ref "U2") (pin "29_1") (pinfunction "GND_29_1") (pintype "power_in"))
      (node (ref "U2") (pin "29_2") (pinfunction "GND_29_2") (pintype "power_in"))
      (node (ref "U2") (pin "29_3") (pinfunction "GND_29_3") (pintype "power_in"))
      (node (ref "U2") (pin "29_4") (pinfunction "GND_29_4") (pintype "power_in"))
      (node (ref "U2") (pin "29_5") (pinfunction "GND_29_5") (pintype "power_in"))
      (node (ref "U2") (pin "29_6") (pinfunction "GND_29_6") (pintype "power_in"))
      (node (ref "U2") (pin "29_7") (pinfunction "GND_29_7") (pintype "power_in"))
      (node (ref "U2") (pin "29_8") (pinfunction "GND_29_8") (pintype "power_in"))
      (node (ref "U2") (pin "29_9") (pinfunction "GND_29_9") (pintype "power_in"))
      (node (ref "U3") (pin "13") (pinfunction "GND_13") (pintype "power_in"))
      (node (ref "U4") (pin "1") (pinfunction "CTG_1") (pintype "power_in"))
      (node (ref "U4") (pin "4") (pinfunction "GND_4") (pintype "power_in"))
      (node (ref "U4") (pin "6") (pinfunction "QSTRT_6") (pintype "input"))
      (node (ref "U4") (pin "9") (pinfunction "EP_9") (pintype "power_in"))
    )
    (net (code "14") (name "GPIO8") (class "Default")
      (node (ref "R1") (pin "2") (pinfunction "2_2") (pintype "passive"))
      (node (ref "U2") (pin "10") (pinfunction "IO8_10") (pintype "bidirectional"))
    )
    (net (code "15") (name "I2C_PW") (class "Default")
      (node (ref "C1") (pin "1") (pinfunction "1_1") (pintype "passive"))
      (node (ref "C2") (pin "1") (pinfunction "1_1") (pintype "passive"))
      (node (ref "R1_PINH") (pin "2") (pinfunction "2_2") (pintype "passive"))
      (node (ref "R2_PINH") (pin "2") (pinfunction "2_2") (pintype "passive"))
      (node (ref "SENSOR2") (pin "2") (pinfunction "CSB_2") (pintype "input"))
      (node (ref "SENSOR2") (pin "6") (pinfunction "VDDIO_6") (pintype "power_in"))
      (node (ref "SENSOR2") (pin "8") (pinfunction "VDD_8") (pintype "power_in"))
      (node (ref "U2") (pin "17") (pinfunction "IO19_17") (pintype "bidirectional"))
    )
    (net (code "16") (name "INT_RTC") (class "Default")
      (node (ref "R1_PINH1") (pin "1") (pinfunction "1_1") (pintype "passive"))
      (node (ref "TP15") (pin "TP") (pinfunction "TP_TP") (pintype "input"))
      (node (ref "U2") (pin "8") (pinfunction "IO0_8") (pintype "bidirectional"))
      (node (ref "U3") (pin "3") (pinfunction "SQW/~{INT}_3") (pintype "output"))
    )
    (net (code "17") (name "IO{slash}BOOT") (class "Default")
      (node (ref "BOOT_BUTTON") (pin "3") (pinfunction "3_3") (pintype "passive"))
      (node (ref "BOOT_BUTTON") (pin "4") (pinfunction "4_4") (pintype "passive"))
      (node (ref "C6") (pin "1") (pinfunction "1_1") (pintype "passive"))
      (node (ref "R_BOOT") (pin "2") (pinfunction "2_2") (pintype "passive"))
      (node (ref "U2") (pin "15") (pinfunction "IO9_15") (pintype "bidirectional"))
    )
    (net (code "18") (name "IO{slash}CHANGE") (class "Default")
      (node (ref "C10") (pin "1") (pinfunction "1_1") (pintype "passive"))
      (node (ref "CHANGE_BUTTON") (pin "3") (pinfunction "3_3") (pintype "passive"))
      (node (ref "CHANGE_BUTTON") (pin "4") (pinfunction "4_4") (pintype "passive"))
      (node (ref "R_CHANGE") (pin "2") (pinfunction "2_2") (pintype "passive"))
      (node (ref "U2") (pin "23") (pinfunction "IO15_23") (pintype "bidirectional"))
    )
    (net (code "19") (name "MISO") (class "Default")
      (node (ref "D12") (pin "1") (pinfunction "1_1") (pintype "passive"))
      (node (ref "J4") (pin "P7") (pinfunction "DAT0_P7") (pintype "bidirectional"))
      (node (ref "R8") (pin "1") (pinfunction "1_1") (pintype "passive"))
      (node (ref "TP6") (pin "TP") (pinfunction "TP_TP") (pintype "input"))
      (node (ref "U1") (pin "2") (pinfunction "DO(IO1)_2") (pintype "bidirectional"))
      (node (ref "U2") (pin "27") (pinfunction "IO2_27") (pintype "bidirectional"))
    )
    (net (code "20") (name "MOSI") (class "Default")
      (node (ref "D11") (pin "1") (pinfunction "1_1") (pintype "passive"))
      (node (ref "J1") (pin "14") (pinfunction "14_14") (pintype "bidirectional"))
      (node (ref "J4") (pin "P3") (pinfunction "CMD_P3") (pintype "bidirectional"))
      (node (ref "R7") (pin "1") (pinfunction "1_1") (pintype "passive"))
      (node (ref "TP7") (pin "TP") (pinfunction "TP_TP") (pintype "input"))
      (node (ref "U1") (pin "5") (pinfunction "DI(IO0)_5") (pintype "bidirectional"))
      (node (ref "U2") (pin "7") (pinfunction "IO7_7") (pintype "bidirectional"))
    )
    (net (code "21") (name "Net-(CHG_LED-PadC)") (class "Default")
      (node (ref "CHG_LED") (pin "C") (pinfunction "C_C") (pintype "passive"))
      (node (ref "R1_BAT") (pin "2") (pinfunction "2_2") (pintype "passive"))
    )
    (net (code "22") (name "Net-(D2-CATHODE)") (class "Default")
      (node (ref "C1_BAT1") (pin "1") (pinfunction "1_1") (pintype "passive"))
      (node (ref "D2") (pin "1") (pinfunction "CATHODE_1") (pintype "bidirectional"))
      (node (ref "IC4") (pin "1") (pinfunction "VIN_1") (pintype "bidirectional"))
      (node (ref "IC4") (pin "3") (pinfunction "CE_3") (pintype "bidirectional"))
      (node (ref "Q1") (pin "2") (pinfunction "S_2") (pintype "bidirectional"))
    )
    (net (code "23") (name "Net-(D3\\-A)") (class "Default")
      (node (ref "C4") (pin "1") (pinfunction "1_1") (pintype "passive"))
      (node (ref "D3\\") (pin "2") (pinfunction "A_2") (pintype "bidirectional"))
      (node (ref "D4") (pin "1") (pinfunction "K_1") (pintype "bidirectional"))
    )
    (net (code "24") (name "Net-(D7-CATHODE)") (class "Default")
      (node (ref "D7") (pin "1") (pinfunction "CATHODE_1") (pintype "bidirectional"))
      (node (ref "R_CAPACITOR") (pin "2") (pinfunction "2_2") (pintype "passive"))
    )
    (net (code "25") (name "Net-(EPD_C1-Pad1)") (class "Default")
      (node (ref "EPD_C1") (pin "1") (pinfunction "1_1") (pintype "passive"))
      (node (ref "J1") (pin "4") (pinfunction "4_4") (pintype "bidirectional"))
    )
    (net (code "26") (name "Net-(EPD_C2-Pad1)") (class "Default")
      (node (ref "EPD_C2") (pin "1") (pinfunction "1_1") (pintype "passive"))
      (node (ref "J1") (pin "5") (pinfunction "5_5") (pintype "bidirectional"))
    )
    (net (code "27") (name "Net-(EPD_C5-Pad1)") (class "Default")
      (node (ref "EPD_C5") (pin "1") (pinfunction "1_1") (pintype "passive"))
      (node (ref "J1") (pin "15") (pinfunction "15_15") (pintype "bidirectional"))
    )
    (net (code "28") (name "Net-(EPD_C6-Pad1)") (class "Default")
      (node (ref "EPD_C6") (pin "1") (pinfunction "1_1") (pintype "passive"))
      (node (ref "J1") (pin "18") (pinfunction "18_18") (pintype "bidirectional"))
    )
    (net (code "29") (name "Net-(EPD_C7-Pad1)") (class "Default")
      (node (ref "EPD_C7") (pin "1") (pinfunction "1_1") (pintype "passive"))
      (node (ref "J1") (pin "19") (pinfunction "19_19") (pintype "bidirectional"))
    )
    (net (code "30") (name "Net-(EPD_C8-Pad1)") (class "Default")
      (node (ref "EPD_C8") (pin "1") (pinfunction "1_1") (pintype "passive"))
      (node (ref "J1") (pin "20") (pinfunction "20_20") (pintype "bidirectional"))
    )
    (net (code "31") (name "Net-(EPD_C10-Pad1)") (class "Default")
      (node (ref "EPD_C10") (pin "1") (pinfunction "1_1") (pintype "passive"))
      (node (ref "J1") (pin "22") (pinfunction "22_22") (pintype "bidirectional"))
    )
    (net (code "32") (name "Net-(EPD_C12-Pad1)") (class "Default")
      (node (ref "EPD_C12") (pin "1") (pinfunction "1_1") (pintype "passive"))
      (node (ref "J1") (pin "24") (pinfunction "24_24") (pintype "bidirectional"))
    )
    (net (code "33") (name "Net-(IC1-CT)") (class "Default")
      (node (ref "C_DELAY") (pin "1") (pinfunction "1_1") (pintype "passive"))
      (node (ref "IC1") (pin "5") (pinfunction "CT_5") (pintype "bidirectional"))
    )
    (net (code "34") (name "Net-(J2-PadA5)") (class "Default")
      (node (ref "J2") (pin "A5") (pinfunction "A5_A5") (pintype "bidirectional"))
      (node (ref "R2-USB1") (pin "2") (pinfunction "2_2") (pintype "passive"))
    )
    (net (code "35") (name "Net-(J2-PadB5)") (class "Default")
      (node (ref "J2") (pin "B5") (pinfunction "B5_B5") (pintype "bidirectional"))
      (node (ref "R2-USB") (pin "1") (pinfunction "1_1") (pintype "passive"))
    )
    (net (code "36") (name "Net-(MCP73831-PROG)") (class "Default")
      (node (ref "MCP73831") (pin "5") (pinfunction "PROG_5") (pintype "input"))
      (node (ref "R2_BAT") (pin "2") (pinfunction "2_2") (pintype "passive"))
    )
    (net (code "37") (name "Net-(MCP73831-STAT)") (class "Default")
      (node (ref "MCP73831") (pin "1") (pinfunction "STAT_1") (pintype "output"))
      (node (ref "R1_BAT") (pin "1") (pinfunction "1_1") (pintype "passive"))
    )
    (net (code "38") (name "PREVGH") (class "Default")
      (node (ref "D5") (pin "1") (pinfunction "K_1") (pintype "bidirectional"))
      (node (ref "EPD_C9") (pin "1") (pinfunction "1_1") (pintype "passive"))
      (node (ref "J1") (pin "21") (pinfunction "21_21") (pintype "bidirectional"))
    )
    (net (code "39") (name "PREVGL") (class "Default")
      (node (ref "D4") (pin "2") (pinfunction "A_2") (pintype "bidirectional"))
      (node (ref "EPD_C11") (pin "1") (pinfunction "1_1") (pintype "passive"))
      (node (ref "J1") (pin "23") (pinfunction "23_23") (pintype "bidirectional"))
    )
    (net (code "40") (name "RESE") (class "Default")
      (node (ref "J1") (pin "3") (pinfunction "3_3") (pintype "bidirectional"))
      (node (ref "Q3") (pin "2") (pinfunction "S_2") (pintype "bidirectional"))
      (node (ref "R3") (pin "1") (pinfunction "1_1") (pintype "passive"))
    )
    (net (code "41") (name "RESE'") (class "Default")
      (node (ref "R2") (pin "2") (pinfunction "2_2") (pintype "passive"))
      (node (ref "R3") (pin "2") (pinfunction "2_2") (pintype "passive"))
      (node (ref "SJ1") (pin "2") (pinfunction "2_2") (pintype "passive"))
    )
    (net (code "42") (name "RESET") (class "Default")
      (node (ref "C5") (pin "1") (pinfunction "1_1") (pintype "passive"))
      (node (ref "IC1") (pin "1") (pinfunction "VOUT_1") (pintype "bidirectional"))
      (node (ref "RESET_BUTTON") (pin "3") (pinfunction "3_3") (pintype "passive"))
      (node (ref "RESET_BUTTON") (pin "4") (pinfunction "4_4") (pintype "passive"))
      (node (ref "R_RESET") (pin "2") (pinfunction "2_2") (pintype "passive"))
      (node (ref "U2") (pin "3") (pinfunction "EN_3") (pintype "input"))
    )
    (net (code "43") (name "RTC_RST") (class "Default")
      (node (ref "U2") (pin "16") (pinfunction "IO18_16") (pintype "bidirectional"))
      (node (ref "U3") (pin "4") (pinfunction "~{RST}_4") (pintype "input"))
    )
    (net (code "44") (name "RX") (class "Default")
      (node (ref "TP2") (pin "TP") (pinfunction "TP_TP") (pintype "input"))
      (node (ref "U2") (pin "24") (pinfunction "RXD0/GPIO17_24") (pintype "bidirectional"))
    )
    (net (code "45") (name "SCK") (class "Default")
      (node (ref "D10") (pin "1") (pinfunction "1_1") (pintype "passive"))
      (node (ref "J1") (pin "13") (pinfunction "13_13") (pintype "bidirectional"))
      (node (ref "J4") (pin "P5") (pinfunction "CLK_P5") (pintype "bidirectional"))
      (node (ref "R6") (pin "1") (pinfunction "1_1") (pintype "passive"))
      (node (ref "TP8") (pin "TP") (pinfunction "TP_TP") (pintype "input"))
      (node (ref "U1") (pin "6") (pinfunction "CLK_6") (pintype "input"))
      (node (ref "U2") (pin "6") (pinfunction "IO6_6") (pintype "bidirectional"))
    )
    (net (code "46") (name "SCL") (class "Default")
      (node (ref "J3") (pin "4") (pinfunction "4_4") (pintype "passive"))
      (node (ref "R2_PINH") (pin "1") (pinfunction "1_1") (pintype "passive"))
      (node (ref "SENSOR2") (pin "4") (pinfunction "SCK_4") (pintype "input"))
      (node (ref "U2") (pin "20") (pinfunction "IO22_20") (pintype "bidirectional"))
      (node (ref "U3") (pin "16") (pinfunction "SCL_16") (pintype "input"))
      (node (ref "U4") (pin "7") (pinfunction "SCL_7") (pintype "input"))
    )
    (net (code "47") (name "SDA") (class "Default")
      (node (ref "J3") (pin "3") (pinfunction "3_3") (pintype "passive"))
      (node (ref "R1_PINH") (pin "1") (pinfunction "1_1") (pintype "passive"))
      (node (ref "SENSOR2") (pin "3") (pinfunction "SDI_3") (pintype "bidirectional"))
      (node (ref "U2") (pin "19") (pinfunction "IO21_19") (pintype "bidirectional"))
      (node (ref "U3") (pin "15") (pinfunction "SDA_15") (pintype "bidirectional"))
      (node (ref "U4") (pin "8") (pinfunction "SDA_8") (pintype "bidirectional"))
    )
    (net (code "48") (name "SRC") (class "Default")
      (node (ref "C4") (pin "2") (pinfunction "2_2") (pintype "passive"))
      (node (ref "D5") (pin "2") (pinfunction "A_2") (pintype "bidirectional"))
      (node (ref "L1") (pin "1") (pinfunction "1_1") (pintype "passive"))
      (node (ref "Q3") (pin "3") (pinfunction "D_3") (pintype "bidirectional"))
    )
    (net (code "49") (name "SS_SD") (class "Default")
      (node (ref "D8") (pin "1") (pinfunction "1_1") (pintype "passive"))
      (node (ref "J4") (pin "P2") (pinfunction "CD/DAT3_P2") (pintype "bidirectional"))
      (node (ref "R10") (pin "1") (pinfunction "1_1") (pintype "passive"))
      (node (ref "U2") (pin "4") (pinfunction "IO4_4") (pintype "bidirectional"))
    )
    (net (code "50") (name "TX") (class "Default")
      (node (ref "TP1") (pin "TP") (pinfunction "TP_TP") (pintype "input"))
      (node (ref "U2") (pin "25") (pinfunction "TXD0/GPIO16_25") (pintype "bidirectional"))
    )
    (net (code "51") (name "USB_D+") (class "Default")
      (node (ref "D1") (pin "1") (pinfunction "I/O1_1_1") (pintype "bidirectional"))
      (node (ref "U2") (pin "14") (pinfunction "IO13_14") (pintype "bidirectional"))
    )
    (net (code "52") (name "USB_D-") (class "Default")
      (node (ref "D1") (pin "3") (pinfunction "I/O2_1_3") (pintype "bidirectional"))
      (node (ref "U2") (pin "13") (pinfunction "IO12_13") (pintype "bidirectional"))
    )
    (net (code "53") (name "VBAT") (class "Default")
      (node (ref "C2_BAT") (pin "1") (pinfunction "1_1") (pintype "passive"))
      (node (ref "MCP73831") (pin "3") (pinfunction "VBAT_3") (pintype "power_in"))
      (node (ref "Q1") (pin "3") (pinfunction "D_3") (pintype "bidirectional"))
      (node (ref "TP3") (pin "TP") (pinfunction "TP_TP") (pintype "input"))
      (node (ref "U4") (pin "2") (pinfunction "CELL_2") (pintype "power_in"))
      (node (ref "U4") (pin "3") (pinfunction "VDD_3") (pintype "power_in"))
    )
    (net (code "54") (name "VBUS") (class "Default")
      (node (ref "C1_BAT") (pin "1") (pinfunction "1_1") (pintype "passive"))
      (node (ref "C4_USB") (pin "1") (pinfunction "1_1") (pintype "passive"))
      (node (ref "C5_USB") (pin "1") (pinfunction "1_1") (pintype "passive"))
      (node (ref "CHG_LED") (pin "A") (pinfunction "A_A") (pintype "passive"))
      (node (ref "D1") (pin "5") (pinfunction "VBUS_5") (pintype "bidirectional"))
      (node (ref "D2") (pin "2") (pinfunction "ANODE_2") (pintype "bidirectional"))
      (node (ref "MCP73831") (pin "4") (pinfunction "VIN_4") (pintype "power_in"))
      (node (ref "PFMF.050.1") (pin "2") (pinfunction "2_2") (pintype "passive"))
      (node (ref "Q1") (pin "1") (pinfunction "G_1") (pintype "bidirectional"))
      (node (ref "R1_PWRUSB") (pin "2") (pinfunction "2_2") (pintype "passive"))
      (node (ref "TP14") (pin "TP") (pinfunction "TP_TP") (pintype "input"))
    )
    (net (code "55") (name "VRTC") (class "Default")
      (node (ref "C10_SUPERCAP") (pin "2") (pinfunction "2_2") (pintype "passive"))
      (node (ref "C8") (pin "1") (pinfunction "1_1") (pintype "passive"))
      (node (ref "R_CAPACITOR") (pin "1") (pinfunction "1_1") (pintype "passive"))
      (node (ref "U3") (pin "14") (pinfunction "VBAT_14") (pintype "power_in"))
    )
    (net (code "56") (name "VUSB") (class "Default")
      (node (ref "J2") (pin "A4") (pinfunction "A4_A4") (pintype "bidirectional"))
      (node (ref "J2") (pin "A9") (pinfunction "A9_A9") (pintype "bidirectional"))
      (node (ref "J2") (pin "B4") (pinfunction "B4_B4") (pintype "bidirectional"))
      (node (ref "J2") (pin "B9") (pinfunction "B9_B9") (pintype "bidirectional"))
      (node (ref "PFMF.050.1") (pin "1") (pinfunction "1_1") (pintype "passive"))
    )
    (net (code "57") (name "unconnected-(IC1-NC-Pad4)") (class "Default")
      (node (ref "IC1") (pin "4") (pinfunction "NC_4") (pintype "no_connect"))
    )
    (net (code "58") (name "unconnected-(IC4-NC-Pad4)") (class "Default")
      (node (ref "IC4") (pin "4") (pinfunction "NC_4") (pintype "no_connect"))
    )
    (net (code "59") (name "unconnected-(J1-Pad1)") (class "Default")
      (node (ref "J1") (pin "1") (pinfunction "1_1") (pintype "bidirectional"))
    )
    (net (code "60") (name "unconnected-(J1-Pad6)") (class "Default")
      (node (ref "J1") (pin "6") (pinfunction "6_6") (pintype "bidirectional"))
    )
    (net (code "61") (name "unconnected-(J1-Pad7)") (class "Default")
      (node (ref "J1") (pin "7") (pinfunction "7_7") (pintype "bidirectional"))
    )
    (net (code "62") (name "unconnected-(J2-PadA8)") (class "Default")
      (node (ref "J2") (pin "A8") (pinfunction "A8_A8") (pintype "bidirectional"))
    )
    (net (code "63") (name "unconnected-(J2-PadB8)") (class "Default")
      (node (ref "J2") (pin "B8") (pinfunction "B8_B8") (pintype "bidirectional"))
    )
    (net (code "64") (name "unconnected-(J4-DAT1-PadP8)") (class "Default")
      (node (ref "J4") (pin "P8") (pinfunction "DAT1_P8") (pintype "bidirectional"))
    )
    (net (code "65") (name "unconnected-(J4-DAT2-PadP1)") (class "Default")
      (node (ref "J4") (pin "P1") (pinfunction "DAT2_P1") (pintype "bidirectional"))
    )
    (net (code "66") (name "unconnected-(J4-DETECTION_1-PadS1)") (class "Default")
      (node (ref "J4") (pin "S1") (pinfunction "DETECTION_1_S1") (pintype "bidirectional"))
    )
    (net (code "67") (name "unconnected-(J4-DETECTION_2-PadS2)") (class "Default")
      (node (ref "J4") (pin "S2") (pinfunction "DETECTION_2_S2") (pintype "bidirectional"))
    )
    (net (code "68") (name "unconnected-(U2-NC-Pad22)") (class "Default")
      (node (ref "U2") (pin "22") (pinfunction "NC_22") (pintype "no_connect"))
    )
    (net (code "69") (name "unconnected-(U4-~{ALERT}-Pad5)") (class "Default")
      (node (ref "U4") (pin "5") (pinfunction "~{ALERT}_5") (pintype "output"))
    )
  )
)
